# meter-sensor-IC.net
KiCad netlist of a schematic drawn in EAGLE
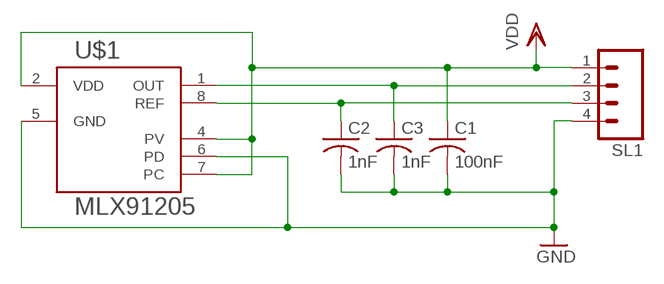
[diagram p0: schematic, sheet 1]

(export (version "E")
  (design (tool "Eeschema 10.0.6"))
  (components
    (comp (ref "C1")
      (value "100nF")
      (footprint "eagle-import:C050-024X044")
      (libsource (lib "eagle-import") (part "C-US050-024X044"))
    )
    (comp (ref "C2")
      (value "1nF")
      (footprint "eagle-import:C025-024X044")
      (libsource (lib "eagle-import") (part "C-US025-024X044"))
    )
    (comp (ref "C3")
      (value "1nF")
      (footprint "eagle-import:C025-024X044")
      (libsource (lib "eagle-import") (part "C-US025-024X044"))
    )
    (comp (ref "SL1")
      (value "M04")
      (footprint "eagle-import:04P")
      (libsource (lib "eagle-import") (part "M04"))
    )
    (comp (ref "U$1")
      (value "MLX91205")
      (footprint "eagle-import:SO08")
      (libsource (lib "eagle-import") (part "MLX91205"))
    )
  )
  (nets
    (net (code "1") (name "GND") (class "Default")
      (node (ref "C1") (pin "2") (pinfunction "2_2") (pintype "passive"))
      (node (ref "C2") (pin "2") (pinfunction "2_2") (pintype "passive"))
      (node (ref "C3") (pin "2") (pinfunction "2_2") (pintype "passive"))
      (node (ref "SL1") (pin "4") (pinfunction "4_4") (pintype "passive"))
      (node (ref "U$1") (pin "5") (pinfunction "GND_5") (pintype "power_in"))
      (node (ref "U$1") (pin "6") (pinfunction "PD_6") (pintype "bidirectional"))
    )
    (net (code "2") (name "Net-(U$1-OUT)") (class "Default")
      (node (ref "C3") (pin "1") (pinfunction "1_1") (pintype "passive"))
      (node (ref "SL1") (pin "2") (pinfunction "2_2") (pintype "passive"))
      (node (ref "U$1") (pin "1") (pinfunction "OUT_1") (pintype "bidirectional"))
    )
    (net (code "3") (name "Net-(U$1-REF)") (class "Default")
      (node (ref "C2") (pin "1") (pinfunction "1_1") (pintype "passive"))
      (node (ref "SL1") (pin "3") (pinfunction "3_3") (pintype "passive"))
      (node (ref "U$1") (pin "8") (pinfunction "REF_8") (pintype "bidirectional"))
    )
    (net (code "4") (name "VDD") (class "Default")
      (node (ref "C1") (pin "1") (pinfunction "1_1") (pintype "passive"))
      (node (ref "SL1") (pin "1") (pinfunction "1_1") (pintype "passive"))
      (node (ref "U$1") (pin "2") (pinfunction "VDD_2") (pintype "power_in"))
      (node (ref "U$1") (pin "4") (pinfunction "PV_4") (pintype "bidirectional"))
      (node (ref "U$1") (pin "7") (pinfunction "PC_7") (pintype "bidirectional"))
    )
  )
)
